# STM32F407.net
KiCad netlist of a schematic drawn in Altium Designer
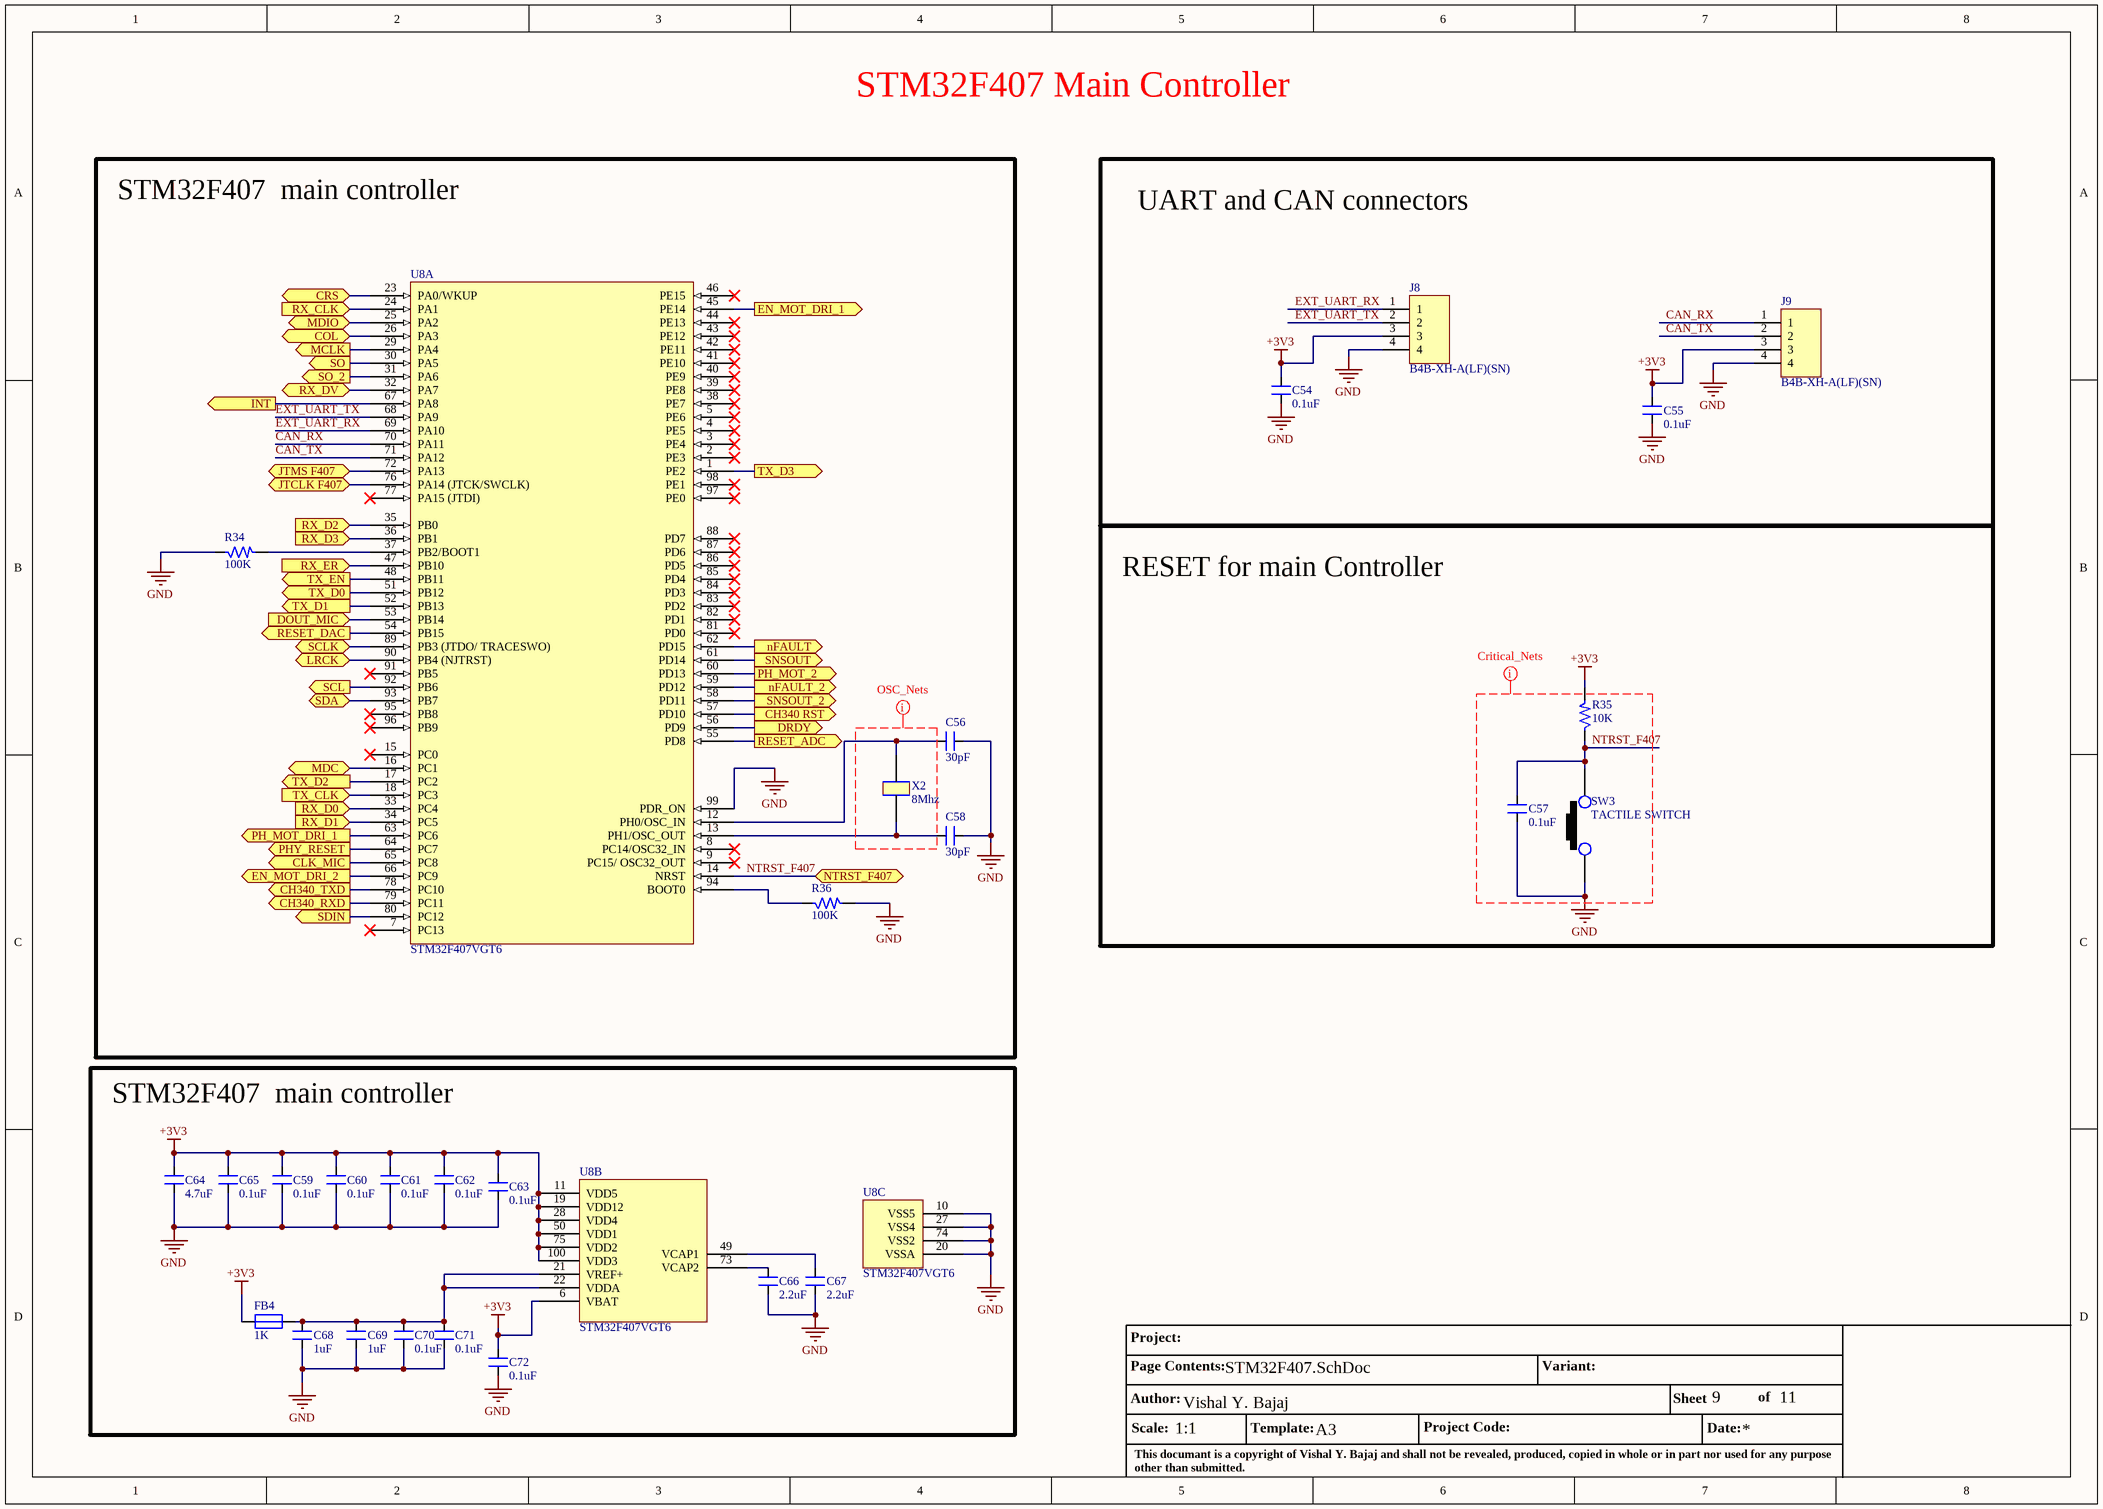
[diagram p0: STM32F407.SchDoc]

(export (version "E")
  (design (tool "Eeschema 10.0.6"))
  (components
    (comp (ref "C54")
      (value "0.1uF")
      (footprint "CAP_0805")
      (description "0.1µF ±5% 50V Ceramic Capacitor X7R 0805 (2012 Metric)")
      (fields
        (field (name "MANUFACTURER") "AVX Corporation")
        (field (name "MANUFACTURER PART NUMBER") "08055C104JAT4A")
      )
      (libsource (lib "ESTEEMPCBLIB") (part "CAP_0.1uF-50V-5%-0805"))
    )
    (comp (ref "C55")
      (value "0.1uF")
      (footprint "CAP_0805")
      (description "0.1µF ±5% 50V Ceramic Capacitor X7R 0805 (2012 Metric)")
      (fields
        (field (name "MANUFACTURER") "AVX Corporation")
        (field (name "MANUFACTURER PART NUMBER") "08055C104JAT4A")
      )
      (libsource (lib "ESTEEMPCBLIB") (part "CAP_0.1uF-50V-5%-0805"))
    )
    (comp (ref "C56")
      (value "30pF")
      (footprint "CAP_0805")
      (description "±10% 50V Ceramic Capacitor C0G, NP0 0805 (2012 Metric)")
      (fields
        (field (name "MANUFACTURER PART NUMBER") "C0805C300K5GAC7800")
        (field (name "MANUFACTURER") "KEMET")
      )
      (libsource (lib "ESTEEMPCBLIB") (part "CAP_30pF-50V-10%-0805"))
    )
    (comp (ref "C57")
      (value "0.1uF")
      (footprint "CAP_0805")
      (description "0.1µF ±10% 50V Ceramic Capacitor X7R 0805 (2012 Metric)")
      (fields
        (field (name "MANUFACTURER") "Samsung")
        (field (name "MANUFACTURER PART NUMBER") "CL21B104KBCNNNC")
      )
      (libsource (lib "ESTEEMPCBLIB") (part "CAP_0.1uF-50V-10%-0805"))
    )
    (comp (ref "C58")
      (value "30pF")
      (footprint "CAP_0805")
      (description "±10% 50V Ceramic Capacitor C0G, NP0 0805 (2012 Metric)")
      (fields
        (field (name "MANUFACTURER PART NUMBER") "C0805C300K5GAC7800")
        (field (name "MANUFACTURER") "KEMET")
      )
      (libsource (lib "ESTEEMPCBLIB") (part "CAP_30pF-50V-10%-0805"))
    )
    (comp (ref "C59")
      (value "0.1uF")
      (footprint "CAP_0805")
      (description "0.1µF ±10% 50V Ceramic Capacitor X7R 0805 (2012 Metric)")
      (fields
        (field (name "MANUFACTURER") "Samsung")
        (field (name "MANUFACTURER PART NUMBER") "CL21B104KBCNNNC")
      )
      (libsource (lib "ESTEEMPCBLIB") (part "CAP_0.1uF-50V-10%-0805"))
    )
    (comp (ref "C60")
      (value "0.1uF")
      (footprint "CAP_0805")
      (description "0.1µF ±10% 50V Ceramic Capacitor X7R 0805 (2012 Metric)")
      (fields
        (field (name "MANUFACTURER") "Samsung")
        (field (name "MANUFACTURER PART NUMBER") "CL21B104KBCNNNC")
      )
      (libsource (lib "ESTEEMPCBLIB") (part "CAP_0.1uF-50V-10%-0805"))
    )
    (comp (ref "C61")
      (value "0.1uF")
      (footprint "CAP_0805")
      (description "0.1µF ±10% 50V Ceramic Capacitor X7R 0805 (2012 Metric)")
      (fields
        (field (name "MANUFACTURER") "Samsung")
        (field (name "MANUFACTURER PART NUMBER") "CL21B104KBCNNNC")
      )
      (libsource (lib "ESTEEMPCBLIB") (part "CAP_0.1uF-50V-10%-0805"))
    )
    (comp (ref "C62")
      (value "0.1uF")
      (footprint "CAP_0805")
      (description "0.1µF ±10% 50V Ceramic Capacitor X7R 0805 (2012 Metric)")
      (fields
        (field (name "MANUFACTURER") "Samsung")
        (field (name "MANUFACTURER PART NUMBER") "CL21B104KBCNNNC")
      )
      (libsource (lib "ESTEEMPCBLIB") (part "CAP_0.1uF-50V-10%-0805"))
    )
    (comp (ref "C63")
      (value "0.1uF")
      (footprint "CAP_0805")
      (description "0.1µF ±10% 50V Ceramic Capacitor X7R 0805 (2012 Metric)")
      (fields
        (field (name "MANUFACTURER") "Samsung")
        (field (name "MANUFACTURER PART NUMBER") "CL21B104KBCNNNC")
      )
      (libsource (lib "ESTEEMPCBLIB") (part "CAP_0.1uF-50V-10%-0805"))
    )
    (comp (ref "C64")
      (value "4.7uF")
      (footprint "CAP_0805")
      (description "4.7µF ±10% 50V Ceramic Capacitor X5R 0805 (2012 Metric)")
      (fields
        (field (name "MANUFACTURER") "Yageo")
        (field (name "MANUFACTURER PART NUMBER") "GRM21BR61H475KE51L")
      )
      (libsource (lib "ESTEEMPCBLIB") (part "CAP_4.7uF-50V-10%-0805"))
    )
    (comp (ref "C65")
      (value "0.1uF")
      (footprint "CAP_0805")
      (description "0.1µF ±10% 50V Ceramic Capacitor X7R 0805 (2012 Metric)")
      (fields
        (field (name "MANUFACTURER") "Samsung")
        (field (name "MANUFACTURER PART NUMBER") "CL21B104KBCNNNC")
      )
      (libsource (lib "ESTEEMPCBLIB") (part "CAP_0.1uF-50V-10%-0805"))
    )
    (comp (ref "C66")
      (value "2.2uF")
      (footprint "CAP_0805")
      (description "2.2µF ±10% 25V Ceramic Capacitor X7R 0805 (2012 Metric)")
      (fields
        (field (name "MANUFACTURER") "KEMET")
        (field (name "MANUFACTURER PART NUMBER") "CL21B225KAFNFNE")
      )
      (libsource (lib "ESTEEMPCBLIB") (part "CAP_2.2uF-25V-10%-0805"))
    )
    (comp (ref "C67")
      (value "2.2uF")
      (footprint "CAP_0805")
      (description "2.2µF ±10% 25V Ceramic Capacitor X7R 0805 (2012 Metric)")
      (fields
        (field (name "MANUFACTURER") "KEMET")
        (field (name "MANUFACTURER PART NUMBER") "CL21B225KAFNFNE")
      )
      (libsource (lib "ESTEEMPCBLIB") (part "CAP_2.2uF-25V-10%-0805"))
    )
    (comp (ref "C68")
      (value "1uF")
      (footprint "CAP_0805")
      (description "1µF ±5% 50V Ceramic Capacitor X7R 0805 (2012 Metric)")
      (fields
        (field (name "MANUFACTURER") "Samsung")
        (field (name "MANUFACTURER PART NUMBER") "CC0805JKX7R9BB105")
      )
      (libsource (lib "ESTEEMPCBLIB") (part "CAP_1uF-50V-5%-0805"))
    )
    (comp (ref "C69")
      (value "1uF")
      (footprint "CAP_0805")
      (description "1µF ±5% 50V Ceramic Capacitor X7R 0805 (2012 Metric)")
      (fields
        (field (name "MANUFACTURER") "Samsung")
        (field (name "MANUFACTURER PART NUMBER") "CC0805JKX7R9BB105")
      )
      (libsource (lib "ESTEEMPCBLIB") (part "CAP_1uF-50V-5%-0805"))
    )
    (comp (ref "C70")
      (value "0.1uF")
      (footprint "CAP_0805")
      (description "0.1µF ±10% 50V Ceramic Capacitor X7R 0805 (2012 Metric)")
      (fields
        (field (name "MANUFACTURER") "Samsung")
        (field (name "MANUFACTURER PART NUMBER") "CL21B104KBCNNNC")
      )
      (libsource (lib "ESTEEMPCBLIB") (part "CAP_0.1uF-50V-10%-0805"))
    )
    (comp (ref "C71")
      (value "0.1uF")
      (footprint "CAP_0805")
      (description "0.1µF ±10% 50V Ceramic Capacitor X7R 0805 (2012 Metric)")
      (fields
        (field (name "MANUFACTURER") "Samsung")
        (field (name "MANUFACTURER PART NUMBER") "CL21B104KBCNNNC")
      )
      (libsource (lib "ESTEEMPCBLIB") (part "CAP_0.1uF-50V-10%-0805"))
    )
    (comp (ref "C72")
      (value "0.1uF")
      (footprint "CAP_0805")
      (description "0.1µF ±10% 50V Ceramic Capacitor X7R 0805 (2012 Metric)")
      (fields
        (field (name "MANUFACTURER") "Samsung")
        (field (name "MANUFACTURER PART NUMBER") "CL21B104KBCNNNC")
      )
      (libsource (lib "ESTEEMPCBLIB") (part "CAP_0.1uF-50V-10%-0805"))
    )
    (comp (ref "FB4")
      (value "1K")
      (footprint "IND_0805")
      (description "1 kOhms @ 100MHz 1 Power Line Ferrite Bead 0805 (2012 Metric) 1.6A")
      (fields
        (field (name "MANUFACTURER") "Laird")
        (field (name "MANUFACTURER PART NUMBER") "BLM21SP102SH1D")
      )
      (libsource (lib "ESTEEMPCBLIB") (part "FB_1K-100MHZ-1.6A-0805"))
    )
    (comp (ref "J8")
      (value "B4B-XH-A(LF)(SN)")
      (footprint "CON4_100_B4B-XH-A_TH_ST")
      (description "4 Pins, 1 Row 2.54mm Pitch, straight Connector, male")
      (fields (field (name "MANUFACTURER") "Wurth Electronics") (field (name "MATING PART NUMBER") "XHP-4"))
      (libsource (lib "ESTEEMPCBLIB") (part "CON-PLG_4X1-100-ST-TH"))
    )
    (comp (ref "J9")
      (value "B4B-XH-A(LF)(SN)")
      (footprint "CON4_100_B4B-XH-A_TH_ST")
      (description "4 Pins, 1 Row 2.54mm Pitch, straight Connector, male")
      (fields (field (name "MANUFACTURER") "Wurth Electronics") (field (name "MATING PART NUMBER") "XHP-4"))
      (libsource (lib "ESTEEMPCBLIB") (part "CON-PLG_4X1-100-ST-TH"))
    )
    (comp (ref "R34")
      (value "100K")
      (footprint "RES_0805")
      (description "100 kOhms ±1% 0.125W, 1/8W Chip Resistor 0805 (2012 Metric) Automotive AEC-Q200 Thick Film")
      (fields (field (name "MANUFACTURER") "Walsin") (field (name "MANUFACTURER PART NUMBER") "WR08X1003FTL"))
      (libsource (lib "ESTEEMPCBLIB") (part "RES_100K-0.125W-1%-0805"))
    )
    (comp (ref "R35")
      (value "10K")
      (footprint "RES_0805")
      (description "10 kOhms ±1% 0.125W, 1/8W Chip Resistor 0805 (2012 Metric) Automotive AEC-Q200 Thick Film")
      (fields (field (name "MANUFACTURER") "CTS") (field (name "MANUFACTURER PART NUMBER") "WR08X1002FTL"))
      (libsource (lib "ESTEEMPCBLIB") (part "RES_10K-0.125W-1%-0805"))
    )
    (comp (ref "R36")
      (value "100K")
      (footprint "RES_0805")
      (description "100 kOhms ±1% 0.125W, 1/8W Chip Resistor 0805 (2012 Metric) Automotive AEC-Q200 Thick Film")
      (fields (field (name "MANUFACTURER") "Walsin") (field (name "MANUFACTURER PART NUMBER") "WR08X1003FTL"))
      (libsource (lib "ESTEEMPCBLIB") (part "RES_100K-0.125W-1%-0805"))
    )
    (comp (ref "SW3")
      (value "TACTILE SWITCH")
      (footprint "SW_342_SMD")
      (description "Tactile Switch SPST-NO Top Actuated Surface Mount")
      (fields
        (field (name "MANUFACTURER") "ITT C&K")
        (field (name "MANUFACTURER PART NUMBER") "RS-282G05A3-SMRT")
      )
      (libsource (lib "ESTEEMPCBLIB") (part "SW1_RS-282G05A3-SMRT-SMD"))
    )
    (comp (ref "U8")
      (value "STM32F407VGT6")
      (footprint "QFN100_19.6_669_58X10_SMD")
      (description "ARM® Cortex®-M4 STM32F4 Microcontroller IC 32-Bit 168MHz 1MB (1M x 8) FLASH 100-LQFP (14x14)")
      (fields (field (name "MANUFACTURER") "STMicroelectronics"))
      (libsource (lib "ESTEEMPCBLIB") (part "IC_STM32F407VGT6"))
    )
    (comp (ref "X2")
      (value "8Mhz")
      (footprint "XTAL_314_240X47_SMD")
      (description "8MHz ±30ppm Crystal 32pF 60 Ohms HC-49/US")
      (fields
        (field (name "MANUFACTURER") "Fox Electronics")
        (field (name "MANUFACTURER PART NUMBER") "ECS-80-32-5PX-TR")
      )
      (libsource (lib "ESTEEMPCBLIB") (part "XTAL_8MHZ-ECS-80-32-5PX-SMD"))
    )
  )
  (nets
    (net (code "1") (name "+3V3") (class "Default")
      (node (ref "C54") (pin "2") (pinfunction "2_2") (pintype "passive"))
      (node (ref "C55") (pin "2") (pinfunction "2_2") (pintype "passive"))
      (node (ref "C59") (pin "2") (pinfunction "2_2") (pintype "passive"))
      (node (ref "C60") (pin "2") (pinfunction "2_2") (pintype "passive"))
      (node (ref "C61") (pin "2") (pinfunction "2_2") (pintype "passive"))
      (node (ref "C62") (pin "2") (pinfunction "2_2") (pintype "passive"))
      (node (ref "C63") (pin "2") (pinfunction "2_2") (pintype "passive"))
      (node (ref "C64") (pin "2") (pinfunction "2_2") (pintype "passive"))
      (node (ref "C65") (pin "2") (pinfunction "2_2") (pintype "passive"))
      (node (ref "C72") (pin "2") (pinfunction "2_2") (pintype "passive"))
      (node (ref "FB4") (pin "1") (pinfunction "1_1") (pintype "passive"))
      (node (ref "J8") (pin "3") (pinfunction "3_3") (pintype "passive"))
      (node (ref "J9") (pin "3") (pinfunction "3_3") (pintype "passive"))
      (node (ref "R35") (pin "2") (pinfunction "2_2") (pintype "passive"))
      (node (ref "U8") (pin "100") (pinfunction "VDD3_100") (pintype "passive"))
      (node (ref "U8") (pin "11") (pinfunction "VDD5_11") (pintype "passive"))
      (node (ref "U8") (pin "19") (pinfunction "VDD12_19") (pintype "passive"))
      (node (ref "U8") (pin "28") (pinfunction "VDD4_28") (pintype "passive"))
      (node (ref "U8") (pin "50") (pinfunction "VDD1_50") (pintype "passive"))
      (node (ref "U8") (pin "6") (pinfunction "VBAT_6") (pintype "passive"))
      (node (ref "U8") (pin "75") (pinfunction "VDD2_75") (pintype "passive"))
    )
    (net (code "3") (name "/CAN_RX") (class "Default")
      (node (ref "J9") (pin "1") (pinfunction "1_1") (pintype "passive"))
      (node (ref "U8") (pin "70") (pinfunction "PA11_70") (pintype "input"))
    )
    (net (code "4") (name "/CAN_TX") (class "Default")
      (node (ref "J9") (pin "2") (pinfunction "2_2") (pintype "passive"))
      (node (ref "U8") (pin "71") (pinfunction "PA12_71") (pintype "input"))
    )
    (net (code "5") (name "/CH340 RST") (class "Default")
      (node (ref "U8") (pin "57") (pinfunction "PD10_57") (pintype "input"))
    )
    (net (code "6") (name "/CH340_RXD") (class "Default")
      (node (ref "U8") (pin "79") (pinfunction "PC11_79") (pintype "input"))
    )
    (net (code "7") (name "/CH340_TXD") (class "Default")
      (node (ref "U8") (pin "78") (pinfunction "PC10_78") (pintype "input"))
    )
    (net (code "8") (name "/CLK_MIC") (class "Default")
      (node (ref "U8") (pin "65") (pinfunction "PC8_65") (pintype "input"))
    )
    (net (code "9") (name "/COL") (class "Default")
      (node (ref "U8") (pin "26") (pinfunction "PA3_26") (pintype "input"))
    )
    (net (code "10") (name "/CRS") (class "Default")
      (node (ref "U8") (pin "23") (pinfunction "PA0/WKUP_23") (pintype "input"))
    )
    (net (code "11") (name "/DOUT_MIC") (class "Default")
      (node (ref "U8") (pin "53") (pinfunction "PB14_53") (pintype "input"))
    )
    (net (code "12") (name "/DRDY") (class "Default")
      (node (ref "U8") (pin "56") (pinfunction "PD9_56") (pintype "input"))
    )
    (net (code "13") (name "/EN_MOT_DRI_1") (class "Default")
      (node (ref "U8") (pin "45") (pinfunction "PE14_45") (pintype "input"))
    )
    (net (code "14") (name "/EN_MOT_DRI_2") (class "Default")
      (node (ref "U8") (pin "66") (pinfunction "PC9_66") (pintype "input"))
    )
    (net (code "15") (name "/EXT_UART_RX") (class "Default")
      (node (ref "J8") (pin "1") (pinfunction "1_1") (pintype "passive"))
      (node (ref "U8") (pin "69") (pinfunction "PA10_69") (pintype "input"))
    )
    (net (code "16") (name "/EXT_UART_TX") (class "Default")
      (node (ref "J8") (pin "2") (pinfunction "2_2") (pintype "passive"))
      (node (ref "U8") (pin "68") (pinfunction "PA9_68") (pintype "input"))
    )
    (net (code "17") (name "/INT") (class "Default")
      (node (ref "U8") (pin "67") (pinfunction "PA8_67") (pintype "input"))
    )
    (net (code "18") (name "/JTCLK F407") (class "Default")
      (node (ref "U8") (pin "76") (pinfunction "PA14_(JTCK/SWCLK)_76") (pintype "input"))
    )
    (net (code "19") (name "/JTMS F407") (class "Default")
      (node (ref "U8") (pin "72") (pinfunction "PA13_72") (pintype "input"))
    )
    (net (code "20") (name "/LRCK") (class "Default")
      (node (ref "U8") (pin "90") (pinfunction "PB4_(NJTRST)_90") (pintype "input"))
    )
    (net (code "21") (name "/MCLK") (class "Default")
      (node (ref "U8") (pin "29") (pinfunction "PA4_29") (pintype "input"))
    )
    (net (code "22") (name "/MDC") (class "Default")
      (node (ref "U8") (pin "16") (pinfunction "PC1_16") (pintype "input"))
    )
    (net (code "23") (name "/MDIO") (class "Default")
      (node (ref "U8") (pin "25") (pinfunction "PA2_25") (pintype "input"))
    )
    (net (code "24") (name "/NTRST_F407") (class "Default")
      (node (ref "C57") (pin "2") (pinfunction "2_2") (pintype "passive"))
      (node (ref "R35") (pin "1") (pinfunction "1_1") (pintype "passive"))
      (node (ref "SW3") (pin "2") (pinfunction "2_2") (pintype "passive"))
      (node (ref "U8") (pin "14") (pinfunction "NRST_14") (pintype "input"))
    )
    (net (code "25") (name "/PHY_RESET") (class "Default")
      (node (ref "U8") (pin "64") (pinfunction "PC7_64") (pintype "input"))
    )
    (net (code "26") (name "/PH_MOT_2") (class "Default")
      (node (ref "U8") (pin "60") (pinfunction "PD13_60") (pintype "input"))
    )
    (net (code "27") (name "/PH_MOT_DRI_1") (class "Default")
      (node (ref "U8") (pin "63") (pinfunction "PC6_63") (pintype "input"))
    )
    (net (code "28") (name "/RESET_ADC") (class "Default")
      (node (ref "U8") (pin "55") (pinfunction "PD8_55") (pintype "input"))
    )
    (net (code "29") (name "/RESET_DAC") (class "Default")
      (node (ref "U8") (pin "54") (pinfunction "PB15_54") (pintype "input"))
    )
    (net (code "30") (name "/RX_CLK") (class "Default")
      (node (ref "U8") (pin "24") (pinfunction "PA1_24") (pintype "input"))
    )
    (net (code "31") (name "/RX_D0") (class "Default")
      (node (ref "U8") (pin "33") (pinfunction "PC4_33") (pintype "input"))
    )
    (net (code "32") (name "/RX_D1") (class "Default")
      (node (ref "U8") (pin "34") (pinfunction "PC5_34") (pintype "input"))
    )
    (net (code "33") (name "/RX_D2") (class "Default")
      (node (ref "U8") (pin "35") (pinfunction "PB0_35") (pintype "input"))
    )
    (net (code "34") (name "/RX_D3") (class "Default")
      (node (ref "U8") (pin "36") (pinfunction "PB1_36") (pintype "input"))
    )
    (net (code "35") (name "/RX_DV") (class "Default")
      (node (ref "U8") (pin "32") (pinfunction "PA7_32") (pintype "input"))
    )
    (net (code "36") (name "/RX_ER") (class "Default")
      (node (ref "U8") (pin "47") (pinfunction "PB10_47") (pintype "input"))
    )
    (net (code "37") (name "/SCL") (class "Default")
      (node (ref "U8") (pin "92") (pinfunction "PB6_92") (pintype "input"))
    )
    (net (code "38") (name "/SCLK") (class "Default")
      (node (ref "U8") (pin "89") (pinfunction "PB3_(JTDO/_TRACESWO)_89") (pintype "input"))
    )
    (net (code "39") (name "/SDA") (class "Default")
      (node (ref "U8") (pin "93") (pinfunction "PB7_93") (pintype "input"))
    )
    (net (code "40") (name "/SDIN") (class "Default")
      (node (ref "U8") (pin "80") (pinfunction "PC12_80") (pintype "input"))
    )
    (net (code "41") (name "/SNSOUT") (class "Default")
      (node (ref "U8") (pin "61") (pinfunction "PD14_61") (pintype "input"))
    )
    (net (code "42") (name "/SNSOUT_2") (class "Default")
      (node (ref "U8") (pin "58") (pinfunction "PD11_58") (pintype "input"))
    )
    (net (code "43") (name "/SO") (class "Default")
      (node (ref "U8") (pin "30") (pinfunction "PA5_30") (pintype "input"))
    )
    (net (code "44") (name "/SO_2") (class "Default")
      (node (ref "U8") (pin "31") (pinfunction "PA6_31") (pintype "input"))
    )
    (net (code "45") (name "/TX_CLK") (class "Default")
      (node (ref "U8") (pin "18") (pinfunction "PC3_18") (pintype "input"))
    )
    (net (code "46") (name "/TX_D0") (class "Default")
      (node (ref "U8") (pin "51") (pinfunction "PB12_51") (pintype "input"))
    )
    (net (code "47") (name "/TX_D1") (class "Default")
      (node (ref "U8") (pin "52") (pinfunction "PB13_52") (pintype "input"))
    )
    (net (code "48") (name "/TX_D2") (class "Default")
      (node (ref "U8") (pin "17") (pinfunction "PC2_17") (pintype "input"))
    )
    (net (code "49") (name "/TX_D3") (class "Default")
      (node (ref "U8") (pin "1") (pinfunction "PE2_1") (pintype "input"))
    )
    (net (code "50") (name "/TX_EN") (class "Default")
      (node (ref "U8") (pin "48") (pinfunction "PB11_48") (pintype "input"))
    )
    (net (code "51") (name "/nFAULT") (class "Default")
      (node (ref "U8") (pin "62") (pinfunction "PD15_62") (pintype "input"))
    )
    (net (code "52") (name "/nFAULT_2") (class "Default")
      (node (ref "U8") (pin "59") (pinfunction "PD12_59") (pintype "input"))
    )
    (net (code "53") (name "GND") (class "Default")
      (node (ref "C54") (pin "1") (pinfunction "1_1") (pintype "passive"))
      (node (ref "C55") (pin "1") (pinfunction "1_1") (pintype "passive"))
      (node (ref "C56") (pin "2") (pinfunction "2_2") (pintype "passive"))
      (node (ref "C57") (pin "1") (pinfunction "1_1") (pintype "passive"))
      (node (ref "C58") (pin "2") (pinfunction "2_2") (pintype "passive"))
      (node (ref "C59") (pin "1") (pinfunction "1_1") (pintype "passive"))
      (node (ref "C60") (pin "1") (pinfunction "1_1") (pintype "passive"))
      (node (ref "C61") (pin "1") (pinfunction "1_1") (pintype "passive"))
      (node (ref "C62") (pin "1") (pinfunction "1_1") (pintype "passive"))
      (node (ref "C63") (pin "1") (pinfunction "1_1") (pintype "passive"))
      (node (ref "C64") (pin "1") (pinfunction "1_1") (pintype "passive"))
      (node (ref "C65") (pin "1") (pinfunction "1_1") (pintype "passive"))
      (node (ref "C66") (pin "1") (pinfunction "1_1") (pintype "passive"))
      (node (ref "C67") (pin "1") (pinfunction "1_1") (pintype "passive"))
      (node (ref "C68") (pin "1") (pinfunction "1_1") (pintype "passive"))
      (node (ref "C69") (pin "1") (pinfunction "1_1") (pintype "passive"))
      (node (ref "C70") (pin "1") (pinfunction "1_1") (pintype "passive"))
      (node (ref "C71") (pin "1") (pinfunction "1_1") (pintype "passive"))
      (node (ref "C72") (pin "1") (pinfunction "1_1") (pintype "passive"))
      (node (ref "J8") (pin "4") (pinfunction "4_4") (pintype "passive"))
      (node (ref "J9") (pin "4") (pinfunction "4_4") (pintype "passive"))
      (node (ref "R34") (pin "1") (pinfunction "1_1") (pintype "passive"))
      (node (ref "R36") (pin "2") (pinfunction "2_2") (pintype "passive"))
      (node (ref "SW3") (pin "1") (pinfunction "1_1") (pintype "passive"))
      (node (ref "U8") (pin "10") (pinfunction "VSS5_10") (pintype "passive"))
      (node (ref "U8") (pin "20") (pinfunction "VSSA_20") (pintype "passive"))
      (node (ref "U8") (pin "27") (pinfunction "VSS4_27") (pintype "passive"))
      (node (ref "U8") (pin "74") (pinfunction "VSS2_74") (pintype "passive"))
      (node (ref "U8") (pin "99") (pinfunction "PDR_ON_99") (pintype "input"))
    )
    (net (code "54") (name "Net-(U8A-BOOT0)") (class "Default")
      (node (ref "R36") (pin "1") (pinfunction "1_1") (pintype "passive"))
      (node (ref "U8") (pin "94") (pinfunction "BOOT0_94") (pintype "input"))
    )
    (net (code "55") (name "Net-(U8A-PB2{slash}BOOT1)") (class "Default")
      (node (ref "R34") (pin "2") (pinfunction "2_2") (pintype "passive"))
      (node (ref "U8") (pin "37") (pinfunction "PB2/BOOT1_37") (pintype "input"))
    )
    (net (code "56") (name "Net-(U8A-PH0{slash}OSC_IN)") (class "Default")
      (node (ref "C56") (pin "1") (pinfunction "1_1") (pintype "passive"))
      (node (ref "U8") (pin "12") (pinfunction "PH0/OSC_IN_12") (pintype "input"))
      (node (ref "X2") (pin "2") (pinfunction "2_2") (pintype "passive"))
    )
    (net (code "57") (name "Net-(U8A-PH1{slash}OSC_OUT)") (class "Default")
      (node (ref "C58") (pin "1") (pinfunction "1_1") (pintype "passive"))
      (node (ref "U8") (pin "13") (pinfunction "PH1/OSC_OUT_13") (pintype "input"))
      (node (ref "X2") (pin "1") (pinfunction "1_1") (pintype "passive"))
    )
    (net (code "58") (name "Net-(U8B-VCAP1)") (class "Default")
      (node (ref "C67") (pin "2") (pinfunction "2_2") (pintype "passive"))
      (node (ref "U8") (pin "49") (pinfunction "VCAP1_49") (pintype "passive"))
    )
    (net (code "59") (name "Net-(U8B-VCAP2)") (class "Default")
      (node (ref "C66") (pin "2") (pinfunction "2_2") (pintype "passive"))
      (node (ref "U8") (pin "73") (pinfunction "VCAP2_73") (pintype "passive"))
    )
    (net (code "60") (name "Net-(U8B-VDDA)") (class "Default")
      (node (ref "C68") (pin "2") (pinfunction "2_2") (pintype "passive"))
      (node (ref "C69") (pin "2") (pinfunction "2_2") (pintype "passive"))
      (node (ref "C70") (pin "2") (pinfunction "2_2") (pintype "passive"))
      (node (ref "C71") (pin "2") (pinfunction "2_2") (pintype "passive"))
      (node (ref "FB4") (pin "2") (pinfunction "2_2") (pintype "passive"))
      (node (ref "U8") (pin "21") (pinfunction "VREF+_21") (pintype "passive"))
      (node (ref "U8") (pin "22") (pinfunction "VDDA_22") (pintype "passive"))
    )
    (net (code "61") (name "unconnected-(U8A-PA15_(JTDI)-Pad77)") (class "Default")
      (node (ref "U8") (pin "77") (pinfunction "PA15_(JTDI)_77") (pintype "input+no_connect"))
    )
    (net (code "62") (name "unconnected-(U8A-PB5-Pad91)") (class "Default")
      (node (ref "U8") (pin "91") (pinfunction "PB5_91") (pintype "input+no_connect"))
    )
    (net (code "63") (name "unconnected-(U8A-PB8-Pad95)") (class "Default")
      (node (ref "U8") (pin "95") (pinfunction "PB8_95") (pintype "input+no_connect"))
    )
    (net (code "64") (name "unconnected-(U8A-PB9-Pad96)") (class "Default")
      (node (ref "U8") (pin "96") (pinfunction "PB9_96") (pintype "input+no_connect"))
    )
    (net (code "65") (name "unconnected-(U8A-PC0-Pad15)") (class "Default")
      (node (ref "U8") (pin "15") (pinfunction "PC0_15") (pintype "input+no_connect"))
    )
    (net (code "66") (name "unconnected-(U8A-PC13-Pad7)") (class "Default")
      (node (ref "U8") (pin "7") (pinfunction "PC13_7") (pintype "input+no_connect"))
    )
    (net (code "67") (name "unconnected-(U8A-PC14{slash}OSC32_IN-Pad8)") (class "Default")
      (node (ref "U8") (pin "8") (pinfunction "PC14/OSC32_IN_8") (pintype "input+no_connect"))
    )
    (net (code "68") (name "unconnected-(U8A-PC15{slash}_OSC32_OUT-Pad9)") (class "Default")
      (node (ref "U8") (pin "9") (pinfunction "PC15/_OSC32_OUT_9") (pintype "input+no_connect"))
    )
    (net (code "69") (name "unconnected-(U8A-PD0-Pad81)") (class "Default")
      (node (ref "U8") (pin "81") (pinfunction "PD0_81") (pintype "input+no_connect"))
    )
    (net (code "70") (name "unconnected-(U8A-PD1-Pad82)") (class "Default")
      (node (ref "U8") (pin "82") (pinfunction "PD1_82") (pintype "input+no_connect"))
    )
    (net (code "71") (name "unconnected-(U8A-PD2-Pad83)") (class "Default")
      (node (ref "U8") (pin "83") (pinfunction "PD2_83") (pintype "input+no_connect"))
    )
    (net (code "72") (name "unconnected-(U8A-PD3-Pad84)") (class "Default")
      (node (ref "U8") (pin "84") (pinfunction "PD3_84") (pintype "input+no_connect"))
    )
    (net (code "73") (name "unconnected-(U8A-PD4-Pad85)") (class "Default")
      (node (ref "U8") (pin "85") (pinfunction "PD4_85") (pintype "input+no_connect"))
    )
    (net (code "74") (name "unconnected-(U8A-PD5-Pad86)") (class "Default")
      (node (ref "U8") (pin "86") (pinfunction "PD5_86") (pintype "input+no_connect"))
    )
    (net (code "75") (name "unconnected-(U8A-PD6-Pad87)") (class "Default")
      (node (ref "U8") (pin "87") (pinfunction "PD6_87") (pintype "input+no_connect"))
    )
    (net (code "76") (name "unconnected-(U8A-PD7-Pad88)") (class "Default")
      (node (ref "U8") (pin "88") (pinfunction "PD7_88") (pintype "input+no_connect"))
    )
    (net (code "77") (name "unconnected-(U8A-PE0-Pad97)") (class "Default")
      (node (ref "U8") (pin "97") (pinfunction "PE0_97") (pintype "input+no_connect"))
    )
    (net (code "78") (name "unconnected-(U8A-PE1-Pad98)") (class "Default")
      (node (ref "U8") (pin "98") (pinfunction "PE1_98") (pintype "input+no_connect"))
    )
    (net (code "79") (name "unconnected-(U8A-PE3-Pad2)") (class "Default")
      (node (ref "U8") (pin "2") (pinfunction "PE3_2") (pintype "input+no_connect"))
    )
    (net (code "80") (name "unconnected-(U8A-PE4-Pad3)") (class "Default")
      (node (ref "U8") (pin "3") (pinfunction "PE4_3") (pintype "input+no_connect"))
    )
    (net (code "81") (name "unconnected-(U8A-PE5-Pad4)") (class "Default")
      (node (ref "U8") (pin "4") (pinfunction "PE5_4") (pintype "input+no_connect"))
    )
    (net (code "82") (name "unconnected-(U8A-PE6-Pad5)") (class "Default")
      (node (ref "U8") (pin "5") (pinfunction "PE6_5") (pintype "input+no_connect"))
    )
    (net (code "83") (name "unconnected-(U8A-PE7-Pad38)") (class "Default")
      (node (ref "U8") (pin "38") (pinfunction "PE7_38") (pintype "input+no_connect"))
    )
    (net (code "84") (name "unconnected-(U8A-PE8-Pad39)") (class "Default")
      (node (ref "U8") (pin "39") (pinfunction "PE8_39") (pintype "input+no_connect"))
    )
    (net (code "85") (name "unconnected-(U8A-PE9-Pad40)") (class "Default")
      (node (ref "U8") (pin "40") (pinfunction "PE9_40") (pintype "input+no_connect"))
    )
    (net (code "86") (name "unconnected-(U8A-PE10-Pad41)") (class "Default")
      (node (ref "U8") (pin "41") (pinfunction "PE10_41") (pintype "input+no_connect"))
    )
    (net (code "87") (name "unconnected-(U8A-PE11-Pad42)") (class "Default")
      (node (ref "U8") (pin "42") (pinfunction "PE11_42") (pintype "input+no_connect"))
    )
    (net (code "88") (name "unconnected-(U8A-PE12-Pad43)") (class "Default")
      (node (ref "U8") (pin "43") (pinfunction "PE12_43") (pintype "input+no_connect"))
    )
    (net (code "89") (name "unconnected-(U8A-PE13-Pad44)") (class "Default")
      (node (ref "U8") (pin "44") (pinfunction "PE13_44") (pintype "input+no_connect"))
    )
    (net (code "90") (name "unconnected-(U8A-PE15-Pad46)") (class "Default")
      (node (ref "U8") (pin "46") (pinfunction "PE15_46") (pintype "input+no_connect"))
    )
  )
)
